# 433schematic.net
KiCad netlist of a schematic drawn in EAGLE
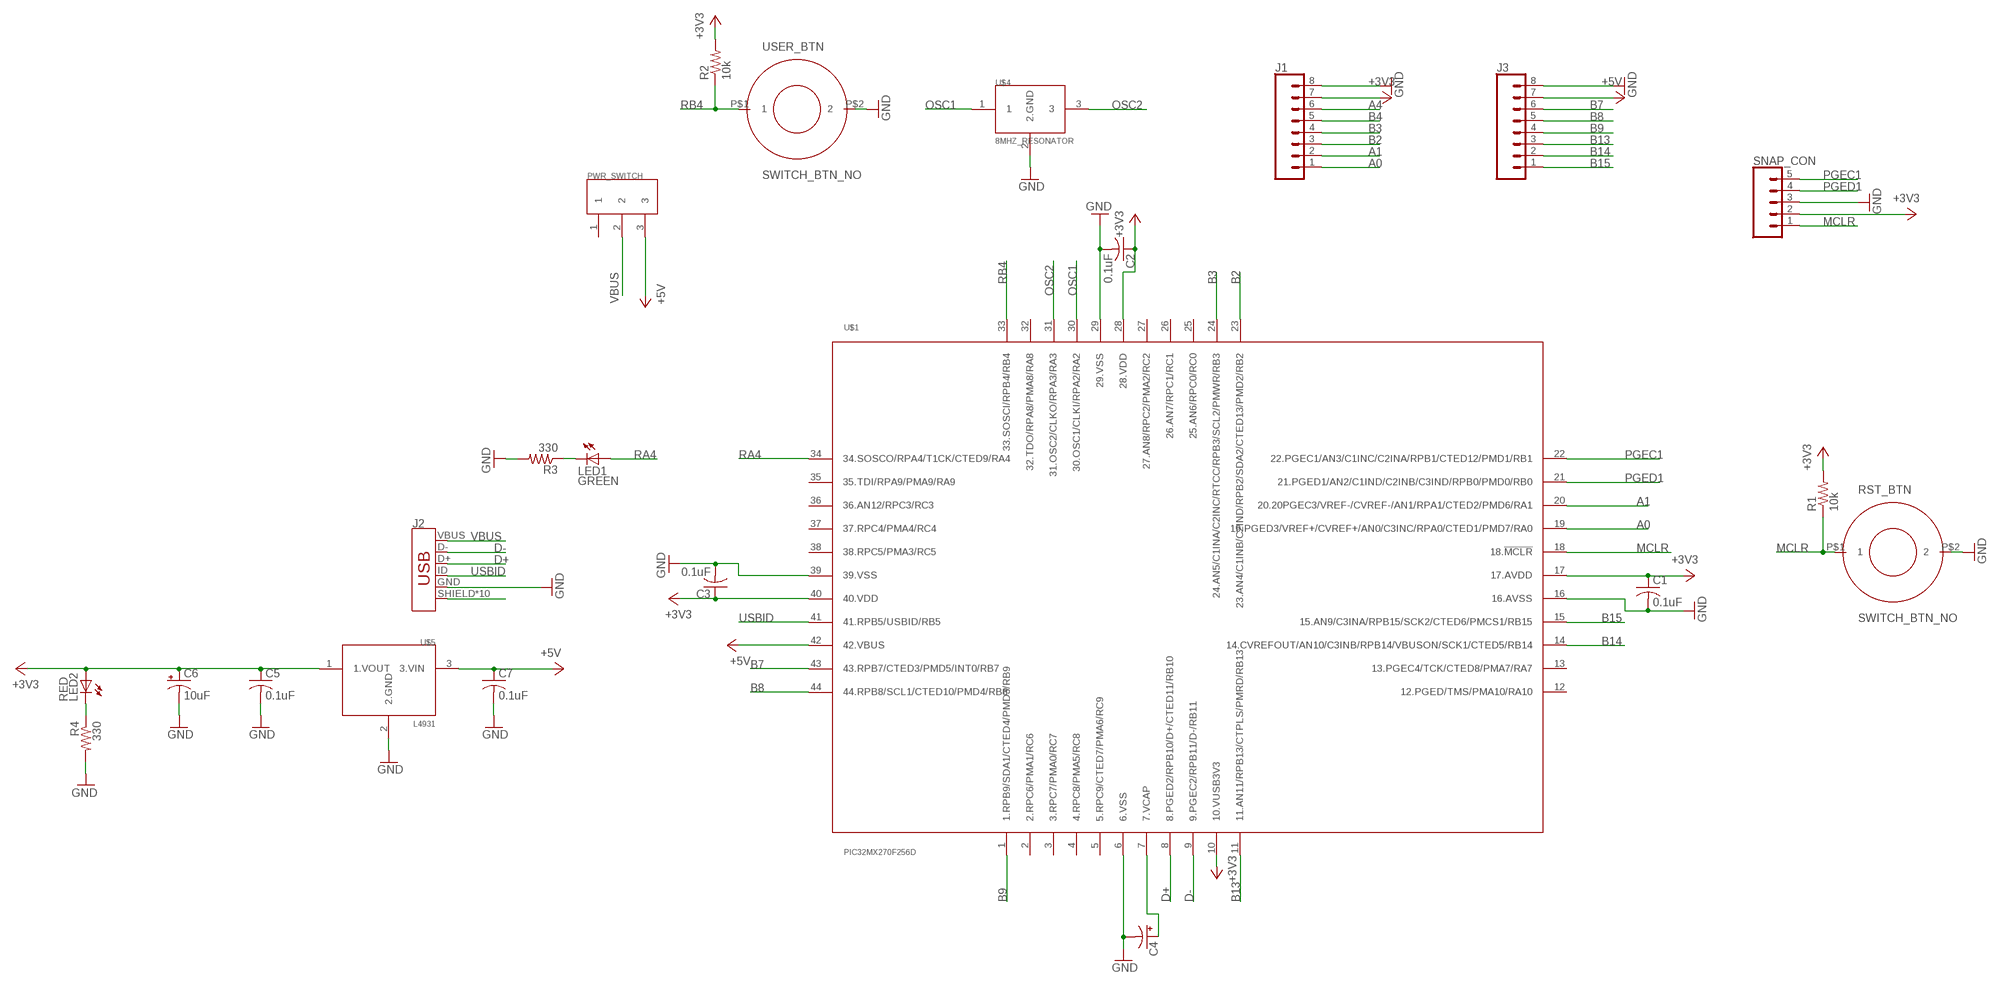
[diagram p0: schematic, sheet 1]

(export (version "E")
  (design (tool "Eeschema 10.0.6"))
  (components
    (comp (ref "C1")
      (value "0.1uF")
      (footprint "eagle-import:C025-024X044")
      (libsource (lib "eagle-import") (part "C-US025-024X044"))
    )
    (comp (ref "C2")
      (value "0.1uF")
      (footprint "eagle-import:C025-024X044")
      (libsource (lib "eagle-import") (part "C-US025-024X044"))
    )
    (comp (ref "C3")
      (value "0.1uF")
      (footprint "eagle-import:C025-024X044")
      (libsource (lib "eagle-import") (part "C-US025-024X044"))
    )
    (comp (ref "C4")
      (value "CPOL-USB45181A")
      (footprint "eagle-import:B45181A")
      (libsource (lib "eagle-import") (part "CPOL-USB45181A"))
    )
    (comp (ref "C5")
      (value "0.1uF")
      (footprint "eagle-import:C025-024X044")
      (libsource (lib "eagle-import") (part "C-US025-024X044"))
    )
    (comp (ref "C6")
      (value "10uF")
      (footprint "eagle-import:B45181A")
      (libsource (lib "eagle-import") (part "CPOL-USB45181A"))
    )
    (comp (ref "C7")
      (value "0.1uF")
      (footprint "eagle-import:C025-024X044")
      (libsource (lib "eagle-import") (part "C-US025-024X044"))
    )
    (comp (ref "J1")
      (value "CONN_08\"")
      (footprint "eagle-import:1X08")
      (libsource (lib "eagle-import") (part "CONN_08{dblquote}"))
    )
    (comp (ref "J2")
      (value "USB_MICRO-B_HALF_PTH_MILL")
      (footprint "eagle-import:USB-MICROB-PTH-MILL")
      (libsource (lib "eagle-import") (part "USB_MICRO-B_HALF_PTH_MILL"))
    )
    (comp (ref "J3")
      (value "CONN_08\"")
      (footprint "eagle-import:1X08")
      (libsource (lib "eagle-import") (part "CONN_08{dblquote}"))
    )
    (comp (ref "LED1")
      (value "GREEN")
      (footprint "eagle-import:LED3MM")
      (libsource (lib "eagle-import") (part "LED3MM"))
    )
    (comp (ref "LED2")
      (value "RED")
      (footprint "eagle-import:LED3MM")
      (libsource (lib "eagle-import") (part "LED3MM"))
    )
    (comp (ref "PWR_SWITCH")
      (value "SLIDE_SWITCH")
      (footprint "eagle-import:SLIDE_SWITCH")
      (libsource (lib "eagle-import") (part "SLIDE_SWITCH"))
    )
    (comp (ref "R1")
      (value "10k")
      (footprint "eagle-import:0204_5")
      (libsource (lib "eagle-import") (part "R-US_0204/5"))
    )
    (comp (ref "R2")
      (value "10k")
      (footprint "eagle-import:0204_5")
      (libsource (lib "eagle-import") (part "R-US_0204/5"))
    )
    (comp (ref "R3")
      (value "330")
      (footprint "eagle-import:0204_5")
      (libsource (lib "eagle-import") (part "R-US_0204/5"))
    )
    (comp (ref "R4")
      (value "330")
      (footprint "eagle-import:0204_5")
      (libsource (lib "eagle-import") (part "R-US_0204/5"))
    )
    (comp (ref "RST_BTN")
      (value "SWITCH_BTN_NO")
      (footprint "eagle-import:BTN_2")
      (libsource (lib "eagle-import") (part "SWITCH_BTN_NO"))
    )
    (comp (ref "SNAP_CON")
      (value "CONN_05")
      (footprint "eagle-import:1X05")
      (libsource (lib "eagle-import") (part "CONN_05"))
    )
    (comp (ref "U$1")
      (value "PIC32MX270F256D")
      (footprint "eagle-import:TQFP44")
      (libsource (lib "eagle-import") (part "PIC32MX270F256D"))
    )
    (comp (ref "U$4")
      (value "8MHZ_RESONATOR")
      (footprint "eagle-import:8MHZ_RESONATOR")
      (libsource (lib "eagle-import") (part "8MHZ_RESONATOR"))
    )
    (comp (ref "U$5")
      (value "L4931")
      (footprint "eagle-import:TO92")
      (libsource (lib "eagle-import") (part "L4931"))
    )
    (comp (ref "USER_BTN")
      (value "SWITCH_BTN_NO")
      (footprint "eagle-import:BTN_2")
      (libsource (lib "eagle-import") (part "SWITCH_BTN_NO"))
    )
  )
  (nets
    (net (code "1") (name "+3V3") (class "Default")
      (node (ref "C1") (pin "1") (pinfunction "1_1") (pintype "passive"))
      (node (ref "C2") (pin "1") (pinfunction "1_1") (pintype "passive"))
      (node (ref "C3") (pin "1") (pinfunction "1_1") (pintype "passive"))
      (node (ref "C5") (pin "1") (pinfunction "1_1") (pintype "passive"))
      (node (ref "C6") (pin "+") (pinfunction "+_+") (pintype "passive"))
      (node (ref "J1") (pin "7") (pinfunction "7_7") (pintype "passive"))
      (node (ref "LED2") (pin "A") (pinfunction "A_A") (pintype "passive"))
      (node (ref "R1") (pin "2") (pinfunction "2_2") (pintype "passive"))
      (node (ref "R2") (pin "2") (pinfunction "2_2") (pintype "passive"))
      (node (ref "SNAP_CON") (pin "2") (pinfunction "2_2") (pintype "passive"))
      (node (ref "U$1") (pin "10") (pinfunction "10.VUSB3V3_10") (pintype "bidirectional"))
      (node (ref "U$1") (pin "17") (pinfunction "17.AVDD_17") (pintype "bidirectional"))
      (node (ref "U$1") (pin "28") (pinfunction "28.VDD_28") (pintype "bidirectional"))
      (node (ref "U$1") (pin "40") (pinfunction "40.VDD_40") (pintype "bidirectional"))
      (node (ref "U$5") (pin "1") (pinfunction "1.VOUT_1") (pintype "bidirectional"))
    )
    (net (code "2") (name "+5V") (class "Default")
      (node (ref "C7") (pin "1") (pinfunction "1_1") (pintype "passive"))
      (node (ref "J3") (pin "7") (pinfunction "7_7") (pintype "passive"))
      (node (ref "PWR_SWITCH") (pin "3") (pinfunction "3_3") (pintype "bidirectional"))
      (node (ref "U$1") (pin "42") (pinfunction "42.VBUS_42") (pintype "bidirectional"))
      (node (ref "U$5") (pin "3") (pinfunction "3.VIN_3") (pintype "bidirectional"))
    )
    (net (code "3") (name "/A0") (class "Default")
      (node (ref "J1") (pin "1") (pinfunction "1_1") (pintype "passive"))
      (node (ref "U$1") (pin "19") (pinfunction "19.PGED3/VREF+/CVREF+/AN0/C3INC/RPA0/CTED1/PMD7/RA0_19") (pintype "bidirectional"))
    )
    (net (code "4") (name "/A1") (class "Default")
      (node (ref "J1") (pin "2") (pinfunction "2_2") (pintype "passive"))
      (node (ref "U$1") (pin "20") (pinfunction "20.20PGEC3/VREF-/CVREF-/AN1/RPA1/CTED2/PMD6/RA1_20") (pintype "bidirectional"))
    )
    (net (code "5") (name "/A4") (class "Default")
      (node (ref "J1") (pin "6") (pinfunction "6_6") (pintype "passive"))
    )
    (net (code "6") (name "/B2") (class "Default")
      (node (ref "J1") (pin "3") (pinfunction "3_3") (pintype "passive"))
      (node (ref "U$1") (pin "23") (pinfunction "23.AN4/C1INB/C2IND/RPB2/SDA2/CTED13/PMD2/RB2_23") (pintype "bidirectional"))
    )
    (net (code "7") (name "/B3") (class "Default")
      (node (ref "J1") (pin "4") (pinfunction "4_4") (pintype "passive"))
      (node (ref "U$1") (pin "24") (pinfunction "24.AN5/C1INA/C2INC/RTCC/RPB3/SCL2/PMWR/RB3_24") (pintype "bidirectional"))
    )
    (net (code "8") (name "/B4") (class "Default")
      (node (ref "J1") (pin "5") (pinfunction "5_5") (pintype "passive"))
    )
    (net (code "9") (name "/B7") (class "Default")
      (node (ref "J3") (pin "6") (pinfunction "6_6") (pintype "passive"))
      (node (ref "U$1") (pin "43") (pinfunction "43.RPB7/CTED3/PMD5/INT0/RB7_43") (pintype "bidirectional"))
    )
    (net (code "10") (name "/B8") (class "Default")
      (node (ref "J3") (pin "5") (pinfunction "5_5") (pintype "passive"))
      (node (ref "U$1") (pin "44") (pinfunction "44.RPB8/SCL1/CTED10/PMD4/RB8_44") (pintype "bidirectional"))
    )
    (net (code "11") (name "/B9") (class "Default")
      (node (ref "J3") (pin "4") (pinfunction "4_4") (pintype "passive"))
      (node (ref "U$1") (pin "1") (pinfunction "1.RPB9/SDA1/CTED4/PMD3/RB9_1") (pintype "bidirectional"))
    )
    (net (code "12") (name "/B13") (class "Default")
      (node (ref "J3") (pin "3") (pinfunction "3_3") (pintype "passive"))
      (node (ref "U$1") (pin "11") (pinfunction "11.AN11/RPB13/CTPLS/PMRD/RB13_11") (pintype "bidirectional"))
    )
    (net (code "13") (name "/B14") (class "Default")
      (node (ref "J3") (pin "2") (pinfunction "2_2") (pintype "passive"))
      (node (ref "U$1") (pin "14") (pinfunction "14.CVREFOUT/AN10/C3INB/RPB14/VBUSON/SCK1/CTED5/RB14_14") (pintype "bidirectional"))
    )
    (net (code "14") (name "/B15") (class "Default")
      (node (ref "J3") (pin "1") (pinfunction "1_1") (pintype "passive"))
      (node (ref "U$1") (pin "15") (pinfunction "15.AN9/C3INA/RPB15/SCK2/CTED6/PMCS1/RB15_15") (pintype "bidirectional"))
    )
    (net (code "15") (name "/D+") (class "Default")
      (node (ref "J2") (pin "D+") (pinfunction "D+_D+") (pintype "bidirectional"))
      (node (ref "U$1") (pin "8") (pinfunction "8.PGED2/RPB10/D+/CTED11/RB10_8") (pintype "bidirectional"))
    )
    (net (code "16") (name "/D-") (class "Default")
      (node (ref "J2") (pin "D-") (pinfunction "D-_D-") (pintype "bidirectional"))
      (node (ref "U$1") (pin "9") (pinfunction "9.PGEC2/RPB11/D-/RB11_9") (pintype "bidirectional"))
    )
    (net (code "17") (name "/MCLR") (class "Default")
      (node (ref "R1") (pin "1") (pinfunction "1_1") (pintype "passive"))
      (node (ref "RST_BTN") (pin "P$1") (pinfunction "1_P$1") (pintype "bidirectional"))
      (node (ref "SNAP_CON") (pin "1") (pinfunction "1_1") (pintype "passive"))
      (node (ref "U$1") (pin "18") (pinfunction "18.~{MCLR}_18") (pintype "bidirectional"))
    )
    (net (code "18") (name "/OSC1") (class "Default")
      (node (ref "U$1") (pin "30") (pinfunction "30.OSC1/CLKI/RPA2/RA2_30") (pintype "bidirectional"))
      (node (ref "U$4") (pin "1") (pinfunction "1_1") (pintype "bidirectional"))
    )
    (net (code "19") (name "/OSC2") (class "Default")
      (node (ref "U$1") (pin "31") (pinfunction "31.OSC2/CLKO/RPA3/RA3_31") (pintype "bidirectional"))
      (node (ref "U$4") (pin "3") (pinfunction "3_3") (pintype "bidirectional"))
    )
    (net (code "20") (name "/PGEC1") (class "Default")
      (node (ref "SNAP_CON") (pin "5") (pinfunction "5_5") (pintype "passive"))
      (node (ref "U$1") (pin "22") (pinfunction "22.PGEC1/AN3/C1INC/C2INA/RPB1/CTED12/PMD1/RB1_22") (pintype "bidirectional"))
    )
    (net (code "21") (name "/PGED1") (class "Default")
      (node (ref "SNAP_CON") (pin "4") (pinfunction "4_4") (pintype "passive"))
      (node (ref "U$1") (pin "21") (pinfunction "21.PGED1/AN2/C1IND/C2INB/C3IND/RPB0/PMD0/RB0_21") (pintype "bidirectional"))
    )
    (net (code "22") (name "/RA4") (class "Default")
      (node (ref "LED1") (pin "A") (pinfunction "A_A") (pintype "passive"))
      (node (ref "U$1") (pin "34") (pinfunction "34.SOSCO/RPA4/T1CK/CTED9/RA4_34") (pintype "bidirectional"))
    )
    (net (code "23") (name "/RB4") (class "Default")
      (node (ref "R2") (pin "1") (pinfunction "1_1") (pintype "passive"))
      (node (ref "U$1") (pin "33") (pinfunction "33.SOSCI/RPB4/RB4_33") (pintype "bidirectional"))
      (node (ref "USER_BTN") (pin "P$1") (pinfunction "1_P$1") (pintype "bidirectional"))
    )
    (net (code "24") (name "/USBID") (class "Default")
      (node (ref "J2") (pin "ID") (pinfunction "ID_ID") (pintype "bidirectional"))
      (node (ref "U$1") (pin "41") (pinfunction "41.RPB5/USBID/RB5_41") (pintype "bidirectional"))
    )
    (net (code "25") (name "/VBUS") (class "Default")
      (node (ref "J2") (pin "VBUS") (pinfunction "VBUS_VBUS") (pintype "power_in"))
      (node (ref "PWR_SWITCH") (pin "2") (pinfunction "2_2") (pintype "bidirectional"))
    )
    (net (code "26") (name "GND") (class "Default")
      (node (ref "C1") (pin "2") (pinfunction "2_2") (pintype "passive"))
      (node (ref "C2") (pin "2") (pinfunction "2_2") (pintype "passive"))
      (node (ref "C3") (pin "2") (pinfunction "2_2") (pintype "passive"))
      (node (ref "C4") (pin "-") (pinfunction "-_-") (pintype "passive"))
      (node (ref "C5") (pin "2") (pinfunction "2_2") (pintype "passive"))
      (node (ref "C6") (pin "-") (pinfunction "-_-") (pintype "passive"))
      (node (ref "C7") (pin "2") (pinfunction "2_2") (pintype "passive"))
      (node (ref "J1") (pin "8") (pinfunction "8_8") (pintype "passive"))
      (node (ref "J2") (pin "GND") (pinfunction "GND_GND") (pintype "power_in"))
      (node (ref "J3") (pin "8") (pinfunction "8_8") (pintype "passive"))
      (node (ref "R3") (pin "2") (pinfunction "2_2") (pintype "passive"))
      (node (ref "R4") (pin "2") (pinfunction "2_2") (pintype "passive"))
      (node (ref "RST_BTN") (pin "P$2") (pinfunction "2_P$2") (pintype "bidirectional"))
      (node (ref "SNAP_CON") (pin "3") (pinfunction "3_3") (pintype "passive"))
      (node (ref "U$1") (pin "16") (pinfunction "16.AVSS_16") (pintype "bidirectional"))
      (node (ref "U$1") (pin "29") (pinfunction "29.VSS_29") (pintype "bidirectional"))
      (node (ref "U$1") (pin "39") (pinfunction "39.VSS_39") (pintype "bidirectional"))
      (node (ref "U$1") (pin "6") (pinfunction "6.VSS_6") (pintype "bidirectional"))
      (node (ref "U$4") (pin "2") (pinfunction "2.GND_2") (pintype "bidirectional"))
      (node (ref "U$5") (pin "2") (pinfunction "2.GND_2") (pintype "bidirectional"))
      (node (ref "USER_BTN") (pin "P$2") (pinfunction "2_P$2") (pintype "bidirectional"))
    )
    (net (code "27") (name "Net-(J2-PadSHIELD)") (class "Default")
      (node (ref "J2") (pin "SHIELD") (pinfunction "SHIELD_SHIELD") (pintype "bidirectional"))
      (node (ref "J2") (pin "SHIELD10") (pinfunction "SHIELD_SHIELD10") (pintype "bidirectional"))
      (node (ref "J2") (pin "SHIELD2") (pinfunction "SHIELD_SHIELD2") (pintype "bidirectional"))
      (node (ref "J2") (pin "SHIELD3") (pinfunction "SHIELD_SHIELD3") (pintype "bidirectional"))
      (node (ref "J2") (pin "SHIELD4") (pinfunction "SHIELD_SHIELD4") (pintype "bidirectional"))
      (node (ref "J2") (pin "SHIELD5") (pinfunction "SHIELD_SHIELD5") (pintype "bidirectional"))
      (node (ref "J2") (pin "SHIELD6") (pinfunction "SHIELD_SHIELD6") (pintype "bidirectional"))
      (node (ref "J2") (pin "SHIELD7") (pinfunction "SHIELD_SHIELD7") (pintype "bidirectional"))
      (node (ref "J2") (pin "SHIELD8") (pinfunction "SHIELD_SHIELD8") (pintype "bidirectional"))
      (node (ref "J2") (pin "SHIELD9") (pinfunction "SHIELD_SHIELD9") (pintype "bidirectional"))
    )
    (net (code "28") (name "Net-(LED1-C)") (class "Default")
      (node (ref "LED1") (pin "K") (pinfunction "C_K") (pintype "passive"))
      (node (ref "R3") (pin "1") (pinfunction "1_1") (pintype "passive"))
    )
    (net (code "29") (name "Net-(LED2-C)") (class "Default")
      (node (ref "LED2") (pin "K") (pinfunction "C_K") (pintype "passive"))
      (node (ref "R4") (pin "1") (pinfunction "1_1") (pintype "passive"))
    )
    (net (code "30") (name "Net-(U$1-7.VCAP)") (class "Default")
      (node (ref "C4") (pin "+") (pinfunction "+_+") (pintype "passive"))
      (node (ref "U$1") (pin "7") (pinfunction "7.VCAP_7") (pintype "bidirectional"))
    )
    (net (code "31") (name "unconnected-(PWR_SWITCH-Pad1)") (class "Default")
      (node (ref "PWR_SWITCH") (pin "1") (pinfunction "1_1") (pintype "bidirectional"))
    )
    (net (code "32") (name "unconnected-(U$1-2.RPC6{slash}PMA1{slash}RC6-Pad2)") (class "Default")
      (node (ref "U$1") (pin "2") (pinfunction "2.RPC6/PMA1/RC6_2") (pintype "bidirectional"))
    )
    (net (code "33") (name "unconnected-(U$1-3.RPC7{slash}PMA0{slash}RC7-Pad3)") (class "Default")
      (node (ref "U$1") (pin "3") (pinfunction "3.RPC7/PMA0/RC7_3") (pintype "bidirectional"))
    )
    (net (code "34") (name "unconnected-(U$1-4.RPC8{slash}PMA5{slash}RC8-Pad4)") (class "Default")
      (node (ref "U$1") (pin "4") (pinfunction "4.RPC8/PMA5/RC8_4") (pintype "bidirectional"))
    )
    (net (code "35") (name "unconnected-(U$1-5.RPC9{slash}CTED7{slash}PMA6{slash}RC9-Pad5)") (class "Default")
      (node (ref "U$1") (pin "5") (pinfunction "5.RPC9/CTED7/PMA6/RC9_5") (pintype "bidirectional"))
    )
    (net (code "36") (name "unconnected-(U$1-12.PGED{slash}TMS{slash}PMA10{slash}RA10-Pad12)") (class "Default")
      (node (ref "U$1") (pin "12") (pinfunction "12.PGED/TMS/PMA10/RA10_12") (pintype "bidirectional"))
    )
    (net (code "37") (name "unconnected-(U$1-13.PGEC4{slash}TCK{slash}CTED8{slash}PMA7{slash}RA7-Pad13)") (class "Default")
      (node (ref "U$1") (pin "13") (pinfunction "13.PGEC4/TCK/CTED8/PMA7/RA7_13") (pintype "bidirectional"))
    )
    (net (code "38") (name "unconnected-(U$1-25.AN6{slash}RPC0{slash}RC0-Pad25)") (class "Default")
      (node (ref "U$1") (pin "25") (pinfunction "25.AN6/RPC0/RC0_25") (pintype "bidirectional"))
    )
    (net (code "39") (name "unconnected-(U$1-26.AN7{slash}RPC1{slash}RC1-Pad26)") (class "Default")
      (node (ref "U$1") (pin "26") (pinfunction "26.AN7/RPC1/RC1_26") (pintype "bidirectional"))
    )
    (net (code "40") (name "unconnected-(U$1-27.AN8{slash}RPC2{slash}PMA2{slash}RC2-Pad27)") (class "Default")
      (node (ref "U$1") (pin "27") (pinfunction "27.AN8/RPC2/PMA2/RC2_27") (pintype "bidirectional"))
    )
    (net (code "41") (name "unconnected-(U$1-32.TDO{slash}RPA8{slash}PMA8{slash}RA8-Pad32)") (class "Default")
      (node (ref "U$1") (pin "32") (pinfunction "32.TDO/RPA8/PMA8/RA8_32") (pintype "bidirectional"))
    )
    (net (code "42") (name "unconnected-(U$1-35.TDI{slash}RPA9{slash}PMA9{slash}RA9-Pad35)") (class "Default")
      (node (ref "U$1") (pin "35") (pinfunction "35.TDI/RPA9/PMA9/RA9_35") (pintype "bidirectional"))
    )
    (net (code "43") (name "unconnected-(U$1-36.AN12{slash}RPC3{slash}RC3-Pad36)") (class "Default")
      (node (ref "U$1") (pin "36") (pinfunction "36.AN12/RPC3/RC3_36") (pintype "bidirectional"))
    )
    (net (code "44") (name "unconnected-(U$1-37.RPC4{slash}PMA4{slash}RC4-Pad37)") (class "Default")
      (node (ref "U$1") (pin "37") (pinfunction "37.RPC4/PMA4/RC4_37") (pintype "bidirectional"))
    )
    (net (code "45") (name "unconnected-(U$1-38.RPC5{slash}PMA3{slash}RC5-Pad38)") (class "Default")
      (node (ref "U$1") (pin "38") (pinfunction "38.RPC5/PMA3/RC5_38") (pintype "bidirectional"))
    )
  )
)
